# RS_transceiver.net
KiCad netlist of a schematic drawn in Altium Designer
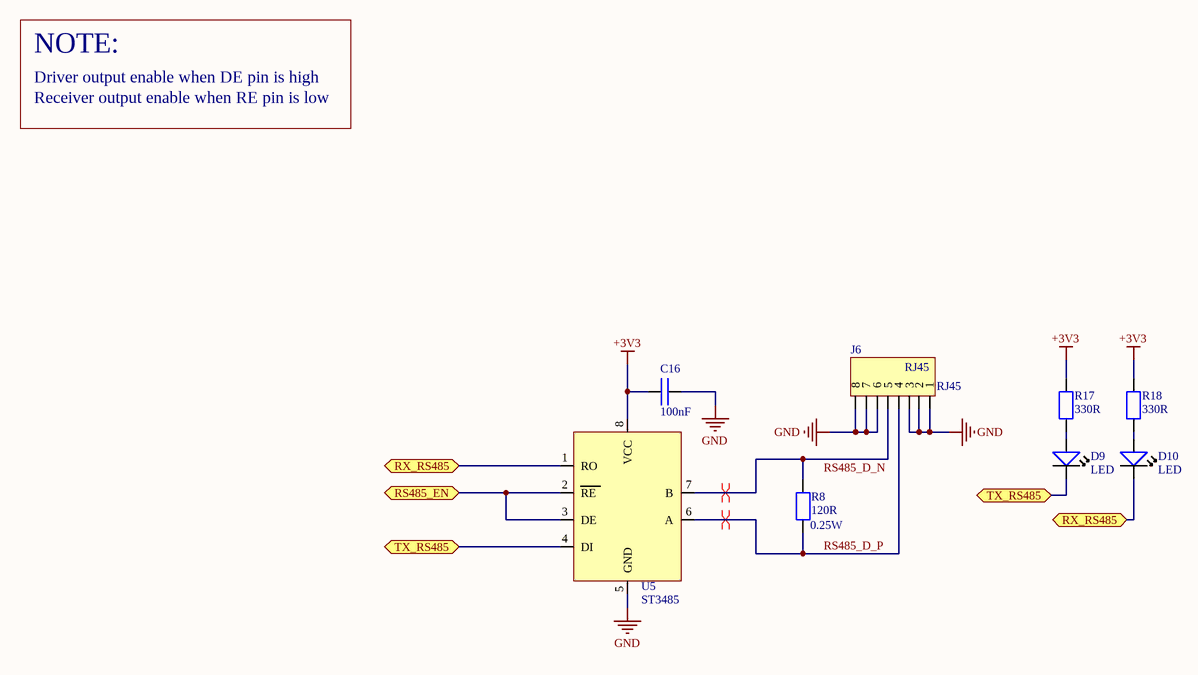
[diagram p0: RS_transceiver.SchDoc]

(export (version "E")
  (design (tool "Eeschema 10.0.6"))
  (components
    (comp (ref "C16") (value "100nF") (footprint "C0603") (libsource (lib "przem_lib") (part "Cap_SMD")))
    (comp (ref "D9") (value "LED") (footprint "LED0805") (libsource (lib "przem_lib") (part "LED")))
    (comp (ref "D10") (value "LED") (footprint "LED0805") (libsource (lib "przem_lib") (part "LED")))
    (comp (ref "J6") (value "RJ45") (footprint "RJ45") (libsource (lib "przem_lib") (part "RJ45")))
    (comp (ref "R8") (value "120R") (footprint "R0805") (libsource (lib "przem_lib") (part "Res")))
    (comp (ref "R17") (value "330R") (footprint "R0805") (libsource (lib "przem_lib") (part "Res")))
    (comp (ref "R18") (value "330R") (footprint "R0805") (libsource (lib "przem_lib") (part "Res")))
    (comp (ref "U5") (value "ST3485") (footprint "SO8") (libsource (lib "przem_lib") (part "ST3485")))
  )
  (nets
    (net (code "1") (name "+3V3") (class "Default")
      (node (ref "C16") (pin "2") (pinfunction "2_2") (pintype "passive"))
      (node (ref "R17") (pin "2") (pinfunction "2_2") (pintype "passive"))
      (node (ref "R18") (pin "2") (pinfunction "2_2") (pintype "passive"))
      (node (ref "U5") (pin "8") (pinfunction "VCC_8") (pintype "passive"))
    )
    (net (code "2") (name "/RS485_D_N") (class "Default")
      (node (ref "J6") (pin "5") (pinfunction "5_5") (pintype "passive"))
      (node (ref "R8") (pin "2") (pinfunction "2_2") (pintype "passive"))
      (node (ref "U5") (pin "7") (pinfunction "B_7") (pintype "passive"))
    )
    (net (code "3") (name "/RS485_D_P") (class "Default")
      (node (ref "J6") (pin "4") (pinfunction "4_4") (pintype "passive"))
      (node (ref "R8") (pin "1") (pinfunction "1_1") (pintype "passive"))
      (node (ref "U5") (pin "6") (pinfunction "A_6") (pintype "passive"))
    )
    (net (code "4") (name "/RS485_EN") (class "Default")
      (node (ref "U5") (pin "2") (pinfunction "RE_2") (pintype "passive"))
      (node (ref "U5") (pin "3") (pinfunction "DE_3") (pintype "passive"))
    )
    (net (code "5") (name "/RX_RS485") (class "Default")
      (node (ref "D10") (pin "K") (pinfunction "K_K") (pintype "passive"))
      (node (ref "U5") (pin "1") (pinfunction "RO_1") (pintype "passive"))
    )
    (net (code "6") (name "/TX_RS485") (class "Default")
      (node (ref "D9") (pin "K") (pinfunction "K_K") (pintype "passive"))
      (node (ref "U5") (pin "4") (pinfunction "DI_4") (pintype "passive"))
    )
    (net (code "7") (name "GND") (class "Default")
      (node (ref "C16") (pin "1") (pinfunction "1_1") (pintype "passive"))
      (node (ref "J6") (pin "1") (pinfunction "1_1") (pintype "passive"))
      (node (ref "J6") (pin "2") (pinfunction "2_2") (pintype "passive"))
      (node (ref "J6") (pin "3") (pinfunction "3_3") (pintype "passive"))
      (node (ref "J6") (pin "6") (pinfunction "6_6") (pintype "passive"))
      (node (ref "J6") (pin "7") (pinfunction "7_7") (pintype "passive"))
      (node (ref "J6") (pin "8") (pinfunction "8_8") (pintype "passive"))
      (node (ref "U5") (pin "5") (pinfunction "GND_5") (pintype "passive"))
    )
    (net (code "8") (name "Net-(D9-PadA)") (class "Default")
      (node (ref "D9") (pin "A") (pinfunction "A_A") (pintype "passive"))
      (node (ref "R17") (pin "1") (pinfunction "1_1") (pintype "passive"))
    )
    (net (code "9") (name "Net-(D10-PadA)") (class "Default")
      (node (ref "D10") (pin "A") (pinfunction "A_A") (pintype "passive"))
      (node (ref "R18") (pin "1") (pinfunction "1_1") (pintype "passive"))
    )
  )
)
